# SparkFun_Air_Quality_ENS160.net
KiCad netlist of a schematic drawn in EAGLE
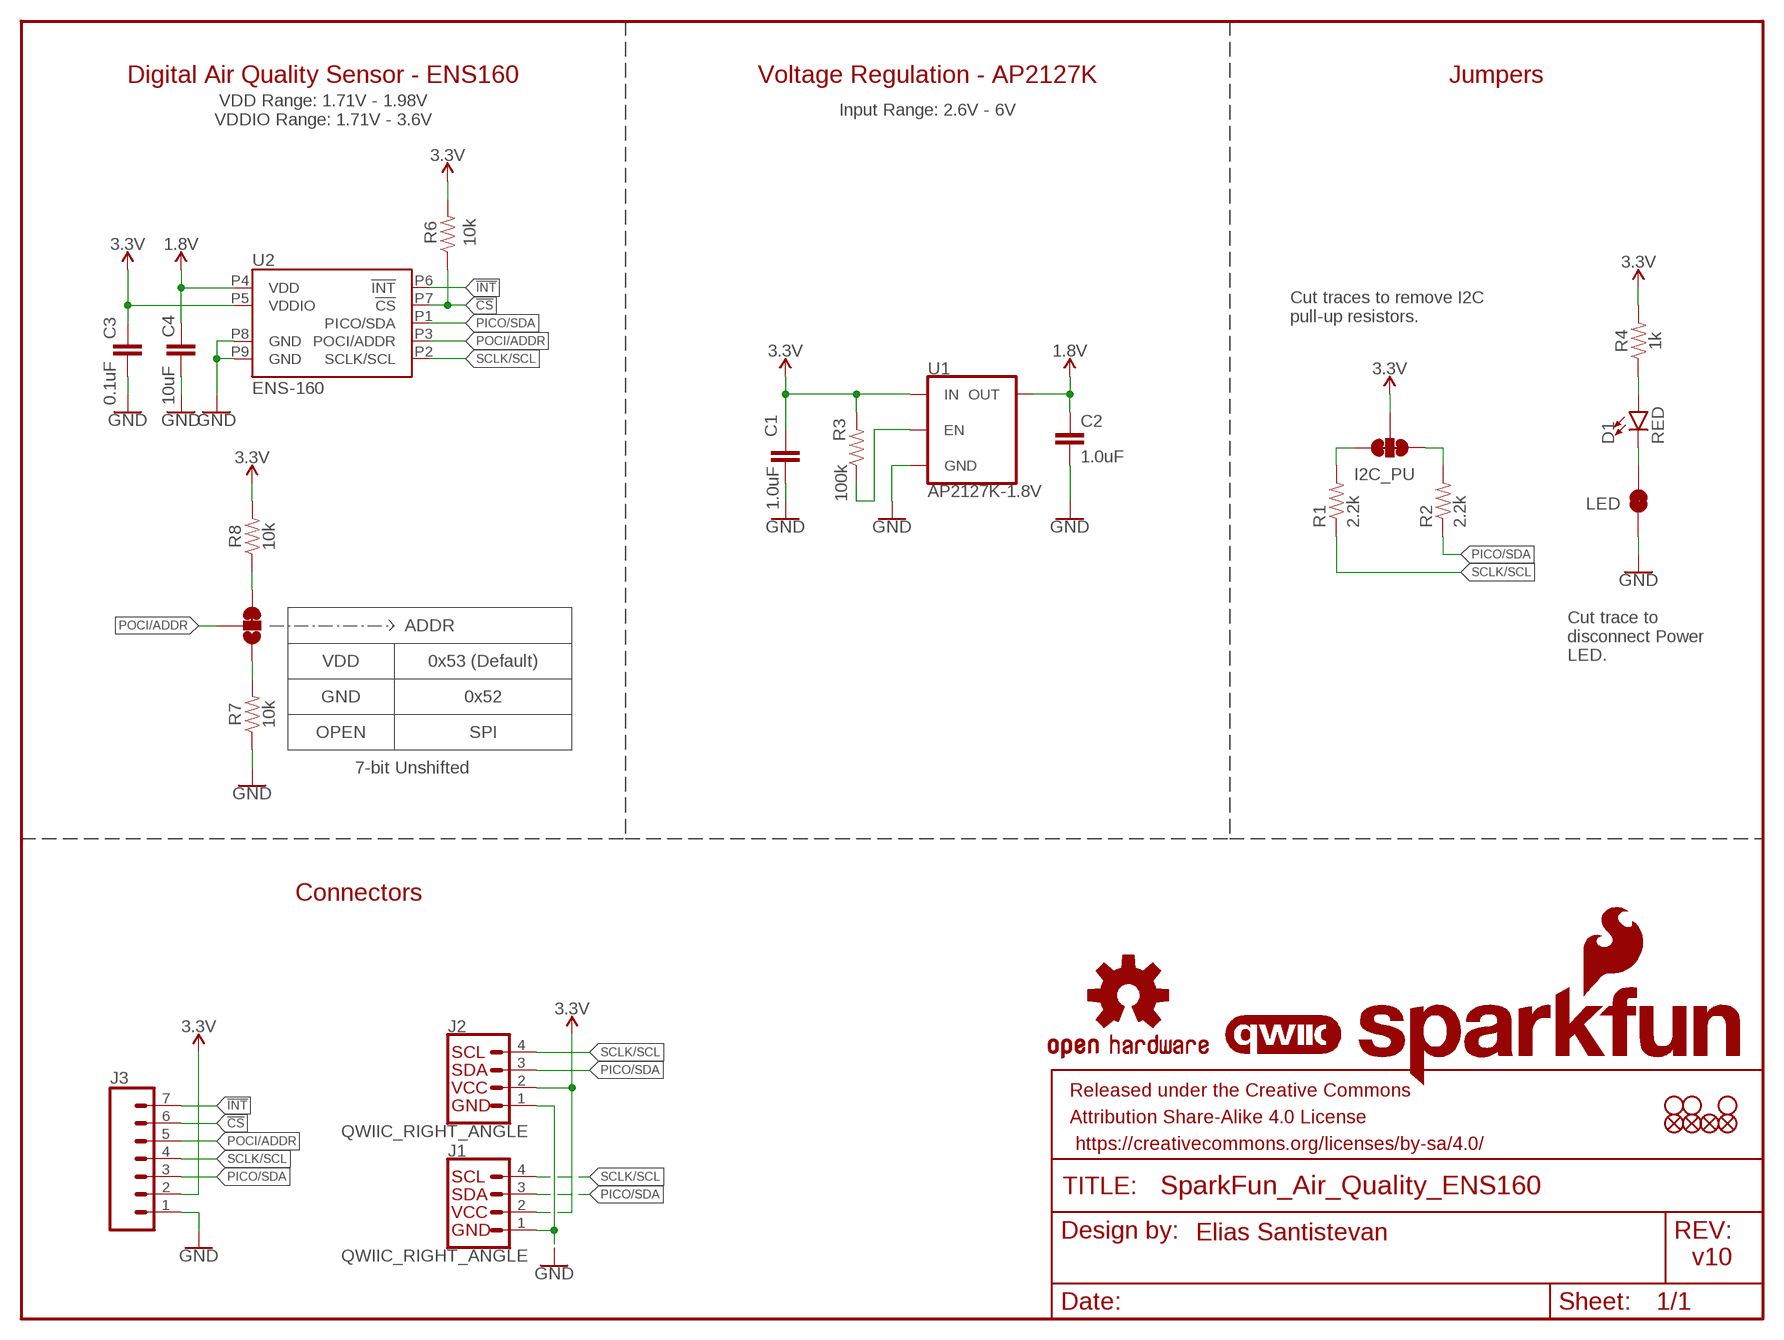
[diagram p0: schematic, sheet 1]

(export (version "E")
  (design (tool "Eeschema 10.0.6"))
  (components
    (comp (ref "ADDR")
      (value "JUMPER-SMT_3_1-NC_TRACE_SILK")
      (footprint "eagle-import:SMT-JUMPER_3_1-NC_TRACE_SILK")
      (libsource (lib "eagle-import") (part "JUMPER-SMT_3_1-NC_TRACE_SILK"))
    )
    (comp (ref "C1")
      (value "1.0uF")
      (footprint "eagle-import:0603")
      (libsource (lib "eagle-import") (part "1.0UF-0603-16V-10%"))
    )
    (comp (ref "C2")
      (value "1.0uF")
      (footprint "eagle-import:0603")
      (libsource (lib "eagle-import") (part "1.0UF-0603-16V-10%"))
    )
    (comp (ref "C3")
      (value "0.1uF")
      (footprint "eagle-import:0603")
      (libsource (lib "eagle-import") (part "0.1UF-0603-25V-(+80/-20%)"))
    )
    (comp (ref "C4")
      (value "10uF")
      (footprint "eagle-import:0603")
      (libsource (lib "eagle-import") (part "10UF-0603-6.3V-20%"))
    )
    (comp (ref "D1")
      (value "RED")
      (footprint "eagle-import:LED-0603")
      (libsource (lib "eagle-import") (part "LED-RED0603"))
    )
    (comp (ref "FD1")
      (value "FIDUCIAL1X2")
      (footprint "eagle-import:FIDUCIAL-1X2")
      (libsource (lib "eagle-import") (part "FIDUCIAL1X2"))
    )
    (comp (ref "FD2")
      (value "FIDUCIAL1X2")
      (footprint "eagle-import:FIDUCIAL-1X2")
      (libsource (lib "eagle-import") (part "FIDUCIAL1X2"))
    )
    (comp (ref "FD3")
      (value "FIDUCIAL1X2")
      (footprint "eagle-import:FIDUCIAL-1X2")
      (libsource (lib "eagle-import") (part "FIDUCIAL1X2"))
    )
    (comp (ref "FD4")
      (value "FIDUCIAL1X2")
      (footprint "eagle-import:FIDUCIAL-1X2")
      (libsource (lib "eagle-import") (part "FIDUCIAL1X2"))
    )
    (comp (ref "FRAME1")
      (value "FRAME-LETTER")
      (footprint "eagle-import:CREATIVE_COMMONS")
      (fields (field (name "DESIGNER") "Elias Santistevan"))
      (libsource (lib "eagle-import") (part "FRAME-LETTER"))
    )
    (comp (ref "I2C_PU")
      (value "S_MODE")
      (footprint "eagle-import:SMT-JUMPER_3_2-NC_TRACE_SILK")
      (libsource (lib "eagle-import") (part "JUMPER-SMT_3_2-NC_TRACE_SILK"))
    )
    (comp (ref "J1")
      (value "QWIIC_RIGHT_ANGLE")
      (footprint "eagle-import:JST04_1MM_RA")
      (libsource (lib "eagle-import") (part "QWIIC_CONNECTORJS-1MM"))
    )
    (comp (ref "J2")
      (value "QWIIC_RIGHT_ANGLE")
      (footprint "eagle-import:JST04_1MM_RA")
      (libsource (lib "eagle-import") (part "QWIIC_CONNECTORJS-1MM"))
    )
    (comp (ref "J3")
      (value "CONN_07NO_SILK")
      (footprint "eagle-import:1X07_NO_SILK")
      (libsource (lib "eagle-import") (part "CONN_07NO_SILK"))
    )
    (comp (ref "LED")
      (value "JUMPER-SMT_2_NC_TRACE_SILK")
      (footprint "eagle-import:SMT-JUMPER_2_NC_TRACE_SILK")
      (libsource (lib "eagle-import") (part "JUMPER-SMT_2_NC_TRACE_SILK"))
    )
    (comp (ref "LOGO2")
      (value "OSHW-LOGOMINI")
      (footprint "eagle-import:OSHW-LOGO-MINI")
      (libsource (lib "eagle-import") (part "OSHW-LOGOMINI"))
    )
    (comp (ref "LOGO3")
      (value "SFE_LOGO_NAME_FLAME.1_INCH")
      (footprint "eagle-import:SFE_LOGO_NAME_FLAME_.1")
      (libsource (lib "eagle-import") (part "SFE_LOGO_NAME_FLAME.1_INCH"))
    )
    (comp (ref "LOGO4")
      (value "QWIIC_LOGO_4MM")
      (footprint "eagle-import:QWIIC_4MM")
      (libsource (lib "eagle-import") (part "QWIIC_LOGO_4MM"))
    )
    (comp (ref "R1")
      (value "2.2k")
      (footprint "eagle-import:0603")
      (libsource (lib "eagle-import") (part "2.2KOHM-0603-1/10W-1%"))
    )
    (comp (ref "R2")
      (value "2.2k")
      (footprint "eagle-import:0603")
      (libsource (lib "eagle-import") (part "2.2KOHM-0603-1/10W-1%"))
    )
    (comp (ref "R3")
      (value "100k")
      (footprint "eagle-import:0603")
      (libsource (lib "eagle-import") (part "100KOHM-0603-1/10W-1%"))
    )
    (comp (ref "R4")
      (value "1k")
      (footprint "eagle-import:0603")
      (libsource (lib "eagle-import") (part "1KOHM-0603-1/10W-1%"))
    )
    (comp (ref "R6")
      (value "10k")
      (footprint "eagle-import:0603")
      (libsource (lib "eagle-import") (part "10KOHM-0603-1/10W-1%"))
    )
    (comp (ref "R7")
      (value "10k")
      (footprint "eagle-import:0603")
      (libsource (lib "eagle-import") (part "10KOHM-0603-1/10W-1%"))
    )
    (comp (ref "R8")
      (value "10k")
      (footprint "eagle-import:0603")
      (libsource (lib "eagle-import") (part "10KOHM-0603-1/10W-1%"))
    )
    (comp (ref "STANDOFF1")
      (value "STAND-OFFTIGHT")
      (footprint "eagle-import:STAND-OFF-TIGHT")
      (libsource (lib "eagle-import") (part "STAND-OFFTIGHT"))
    )
    (comp (ref "STANDOFF2")
      (value "STAND-OFFTIGHT")
      (footprint "eagle-import:STAND-OFF-TIGHT")
      (libsource (lib "eagle-import") (part "STAND-OFFTIGHT"))
    )
    (comp (ref "STANDOFF5")
      (value "STAND-OFFTIGHT")
      (footprint "eagle-import:STAND-OFF-TIGHT")
      (libsource (lib "eagle-import") (part "STAND-OFFTIGHT"))
    )
    (comp (ref "U1")
      (value "AP2127K-1.8V")
      (footprint "eagle-import:SOT23-5")
      (libsource (lib "eagle-import") (part "V_REG_AP2127K-1.8V"))
    )
    (comp (ref "U2")
      (value "ENS-160")
      (footprint "eagle-import:LGA-9")
      (libsource (lib "eagle-import") (part "ENS-160"))
    )
  )
  (nets
    (net (code "1") (name "/~{CS}") (class "Default")
      (node (ref "J3") (pin "6") (pinfunction "6_6") (pintype "passive"))
      (node (ref "R6") (pin "1") (pinfunction "1_1") (pintype "passive"))
      (node (ref "U2") (pin "P7") (pinfunction "~{CS}_P7") (pintype "bidirectional"))
    )
    (net (code "2") (name "/~{INT}") (class "Default")
      (node (ref "J3") (pin "7") (pinfunction "7_7") (pintype "passive"))
      (node (ref "U2") (pin "P6") (pinfunction "~{INT}_P6") (pintype "bidirectional"))
    )
    (net (code "3") (name "1.8V") (class "Default")
      (node (ref "C2") (pin "1") (pinfunction "1_1") (pintype "passive"))
      (node (ref "C4") (pin "1") (pinfunction "1_1") (pintype "passive"))
      (node (ref "U1") (pin "5") (pinfunction "OUT_5") (pintype "passive"))
      (node (ref "U2") (pin "P4") (pinfunction "VDD_P4") (pintype "power_in"))
    )
    (net (code "4") (name "3.3V") (class "Default")
      (node (ref "C1") (pin "1") (pinfunction "1_1") (pintype "passive"))
      (node (ref "C3") (pin "1") (pinfunction "1_1") (pintype "passive"))
      (node (ref "I2C_PU") (pin "2") (pinfunction "2_2") (pintype "passive"))
      (node (ref "J1") (pin "2") (pinfunction "2_2") (pintype "power_in"))
      (node (ref "J2") (pin "2") (pinfunction "2_2") (pintype "power_in"))
      (node (ref "J3") (pin "2") (pinfunction "2_2") (pintype "passive"))
      (node (ref "R3") (pin "2") (pinfunction "2_2") (pintype "passive"))
      (node (ref "R4") (pin "2") (pinfunction "2_2") (pintype "passive"))
      (node (ref "R6") (pin "2") (pinfunction "2_2") (pintype "passive"))
      (node (ref "R8") (pin "2") (pinfunction "2_2") (pintype "passive"))
      (node (ref "U1") (pin "1") (pinfunction "IN_1") (pintype "input"))
      (node (ref "U2") (pin "P5") (pinfunction "VDDIO_P5") (pintype "power_in"))
    )
    (net (code "5") (name "GND") (class "Default")
      (node (ref "C1") (pin "2") (pinfunction "2_2") (pintype "passive"))
      (node (ref "C2") (pin "2") (pinfunction "2_2") (pintype "passive"))
      (node (ref "C3") (pin "2") (pinfunction "2_2") (pintype "passive"))
      (node (ref "C4") (pin "2") (pinfunction "2_2") (pintype "passive"))
      (node (ref "J1") (pin "1") (pinfunction "1_1") (pintype "power_in"))
      (node (ref "J2") (pin "1") (pinfunction "1_1") (pintype "power_in"))
      (node (ref "J3") (pin "1") (pinfunction "1_1") (pintype "passive"))
      (node (ref "LED") (pin "1") (pinfunction "1_1") (pintype "passive"))
      (node (ref "R7") (pin "1") (pinfunction "1_1") (pintype "passive"))
      (node (ref "U1") (pin "2") (pinfunction "GND_2") (pintype "input"))
      (node (ref "U2") (pin "P8") (pinfunction "GND_P8") (pintype "power_in"))
      (node (ref "U2") (pin "P9") (pinfunction "GND_P9") (pintype "power_in"))
    )
    (net (code "6") (name "Net-(ADDR-Pad1)") (class "Default")
      (node (ref "ADDR") (pin "1") (pinfunction "1_1") (pintype "passive"))
      (node (ref "R7") (pin "2") (pinfunction "2_2") (pintype "passive"))
    )
    (net (code "7") (name "Net-(ADDR-Pad3)") (class "Default")
      (node (ref "ADDR") (pin "3") (pinfunction "3_3") (pintype "passive"))
      (node (ref "R8") (pin "1") (pinfunction "1_1") (pintype "passive"))
    )
    (net (code "8") (name "Net-(D1-PadA)") (class "Default")
      (node (ref "D1") (pin "A") (pinfunction "A_A") (pintype "passive"))
      (node (ref "R4") (pin "1") (pinfunction "1_1") (pintype "passive"))
    )
    (net (code "9") (name "Net-(D1-PadC)") (class "Default")
      (node (ref "D1") (pin "C") (pinfunction "C_C") (pintype "passive"))
      (node (ref "LED") (pin "2") (pinfunction "2_2") (pintype "passive"))
    )
    (net (code "10") (name "Net-(I2C_PU-Pad1)") (class "Default")
      (node (ref "I2C_PU") (pin "1") (pinfunction "1_1") (pintype "passive"))
      (node (ref "R1") (pin "2") (pinfunction "2_2") (pintype "passive"))
    )
    (net (code "11") (name "Net-(I2C_PU-Pad3)") (class "Default")
      (node (ref "I2C_PU") (pin "3") (pinfunction "3_3") (pintype "passive"))
      (node (ref "R2") (pin "2") (pinfunction "2_2") (pintype "passive"))
    )
    (net (code "12") (name "Net-(U1-EN)") (class "Default")
      (node (ref "R3") (pin "1") (pinfunction "1_1") (pintype "passive"))
      (node (ref "U1") (pin "3") (pinfunction "EN_3") (pintype "input"))
    )
    (net (code "13") (name "PICO{slash}SDA") (class "Default")
      (node (ref "J1") (pin "3") (pinfunction "3_3") (pintype "passive"))
      (node (ref "J2") (pin "3") (pinfunction "3_3") (pintype "passive"))
      (node (ref "J3") (pin "3") (pinfunction "3_3") (pintype "passive"))
      (node (ref "R2") (pin "1") (pinfunction "1_1") (pintype "passive"))
      (node (ref "U2") (pin "P1") (pinfunction "PICO/SDA_P1") (pintype "bidirectional"))
    )
    (net (code "14") (name "POCI{slash}ADDR") (class "Default")
      (node (ref "ADDR") (pin "2") (pinfunction "2_2") (pintype "passive"))
      (node (ref "J3") (pin "5") (pinfunction "5_5") (pintype "passive"))
      (node (ref "U2") (pin "P3") (pinfunction "POCI/ADDR_P3") (pintype "bidirectional"))
    )
    (net (code "15") (name "SCLK{slash}SCL") (class "Default")
      (node (ref "J1") (pin "4") (pinfunction "4_4") (pintype "passive"))
      (node (ref "J2") (pin "4") (pinfunction "4_4") (pintype "passive"))
      (node (ref "J3") (pin "4") (pinfunction "4_4") (pintype "passive"))
      (node (ref "R1") (pin "1") (pinfunction "1_1") (pintype "passive"))
      (node (ref "U2") (pin "P2") (pinfunction "SCLK/SCL_P2") (pintype "bidirectional"))
    )
  )
)
